# Led.net
KiCad netlist of a schematic drawn in Altium Designer
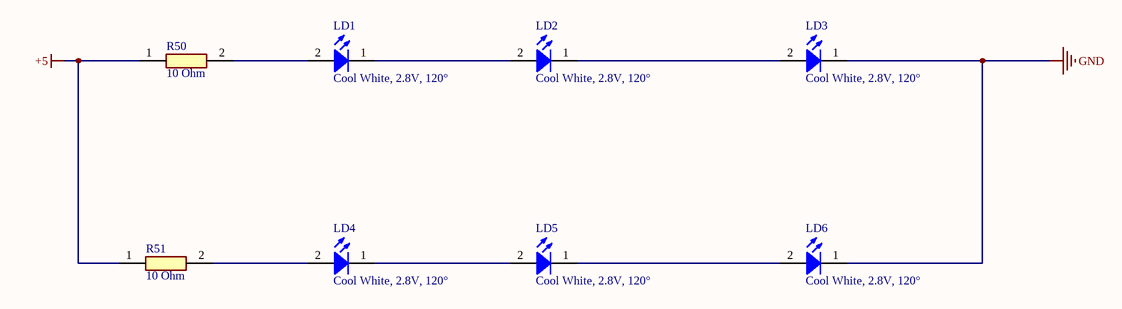
[diagram p0: Led.SchDoc]

(export (version "E")
  (design (tool "Eeschema 10.0.6"))
  (components
    (comp (ref "LD1")
      (value "Cool White, 2.8V, 120°")
      (footprint "WL-SWTP_5630_L5.6W3H0.6")
      (description "WL-SWTP SMT White Top view PLCC, size 5630, Cool White, 2.8V, 120°")
      (fields
        (field (name "MANUFACTURER") "Wurth Elektronik")
        (field (name "MANUFACTURER PART NUMBER") "158563260A")
      )
      (libsource (lib "PO_SS_Lib") (part "158563260A"))
    )
    (comp (ref "LD2")
      (value "Cool White, 2.8V, 120°")
      (footprint "WL-SWTP_5630_L5.6W3H0.6")
      (description "WL-SWTP SMT White Top view PLCC, size 5630, Cool White, 2.8V, 120°")
      (fields
        (field (name "MANUFACTURER") "Wurth Elektronik")
        (field (name "MANUFACTURER PART NUMBER") "158563260A")
      )
      (libsource (lib "PO_SS_Lib") (part "158563260A"))
    )
    (comp (ref "LD3")
      (value "Cool White, 2.8V, 120°")
      (footprint "WL-SWTP_5630_L5.6W3H0.6")
      (description "WL-SWTP SMT White Top view PLCC, size 5630, Cool White, 2.8V, 120°")
      (fields
        (field (name "MANUFACTURER") "Wurth Elektronik")
        (field (name "MANUFACTURER PART NUMBER") "158563260A")
      )
      (libsource (lib "PO_SS_Lib") (part "158563260A"))
    )
    (comp (ref "LD4")
      (value "Cool White, 2.8V, 120°")
      (footprint "WL-SWTP_5630_L5.6W3H0.6")
      (description "WL-SWTP SMT White Top view PLCC, size 5630, Cool White, 2.8V, 120°")
      (fields
        (field (name "MANUFACTURER") "Wurth Elektronik")
        (field (name "MANUFACTURER PART NUMBER") "158563260A")
      )
      (libsource (lib "PO_SS_Lib") (part "158563260A"))
    )
    (comp (ref "LD5")
      (value "Cool White, 2.8V, 120°")
      (footprint "WL-SWTP_5630_L5.6W3H0.6")
      (description "WL-SWTP SMT White Top view PLCC, size 5630, Cool White, 2.8V, 120°")
      (fields
        (field (name "MANUFACTURER") "Wurth Elektronik")
        (field (name "MANUFACTURER PART NUMBER") "158563260A")
      )
      (libsource (lib "PO_SS_Lib") (part "158563260A"))
    )
    (comp (ref "LD6")
      (value "Cool White, 2.8V, 120°")
      (footprint "WL-SWTP_5630_L5.6W3H0.6")
      (description "WL-SWTP SMT White Top view PLCC, size 5630, Cool White, 2.8V, 120°")
      (fields
        (field (name "MANUFACTURER") "Wurth Elektronik")
        (field (name "MANUFACTURER PART NUMBER") "158563260A")
      )
      (libsource (lib "PO_SS_Lib") (part "158563260A"))
    )
    (comp (ref "R50")
      (value "10 Ohm")
      (footprint "Weerstand LEDS")
      (description "Resistor LED")
      (fields (field (name "MANUFACTURER_PART_NUMBER") "EP5WS10RJ"))
      (libsource (lib "PO_SS_Lib") (part "EP5WS10RJ"))
    )
    (comp (ref "R51")
      (value "10 Ohm")
      (footprint "Weerstand LEDS")
      (description "Resistor LED")
      (fields (field (name "MANUFACTURER_PART_NUMBER") "EP5WS10RJ"))
      (libsource (lib "PO_SS_Lib") (part "EP5WS10RJ"))
    )
  )
  (nets
    (net (code "1") (name "+5") (class "Default")
      (node (ref "R50") (pin "1") (pinfunction "1_1") (pintype "passive"))
      (node (ref "R51") (pin "1") (pinfunction "1_1") (pintype "passive"))
    )
    (net (code "2") (name "GND") (class "Default")
      (node (ref "LD3") (pin "1") (pinfunction "K_1") (pintype "passive"))
      (node (ref "LD6") (pin "1") (pinfunction "K_1") (pintype "passive"))
    )
    (net (code "3") (name "Net-(LD1-A)") (class "Default")
      (node (ref "LD1") (pin "2") (pinfunction "A_2") (pintype "passive"))
      (node (ref "R50") (pin "2") (pinfunction "2_2") (pintype "passive"))
    )
    (net (code "4") (name "Net-(LD1-K)") (class "Default")
      (node (ref "LD1") (pin "1") (pinfunction "K_1") (pintype "passive"))
      (node (ref "LD2") (pin "2") (pinfunction "A_2") (pintype "passive"))
    )
    (net (code "5") (name "Net-(LD2-K)") (class "Default")
      (node (ref "LD2") (pin "1") (pinfunction "K_1") (pintype "passive"))
      (node (ref "LD3") (pin "2") (pinfunction "A_2") (pintype "passive"))
    )
    (net (code "6") (name "Net-(LD4-A)") (class "Default")
      (node (ref "LD4") (pin "2") (pinfunction "A_2") (pintype "passive"))
      (node (ref "R51") (pin "2") (pinfunction "2_2") (pintype "passive"))
    )
    (net (code "7") (name "Net-(LD4-K)") (class "Default")
      (node (ref "LD4") (pin "1") (pinfunction "K_1") (pintype "passive"))
      (node (ref "LD5") (pin "2") (pinfunction "A_2") (pintype "passive"))
    )
    (net (code "8") (name "Net-(LD5-K)") (class "Default")
      (node (ref "LD5") (pin "1") (pinfunction "K_1") (pintype "passive"))
      (node (ref "LD6") (pin "2") (pinfunction "A_2") (pintype "passive"))
    )
  )
)
